# Bed_Temp_Controller.net
KiCad netlist of a schematic drawn in EAGLE
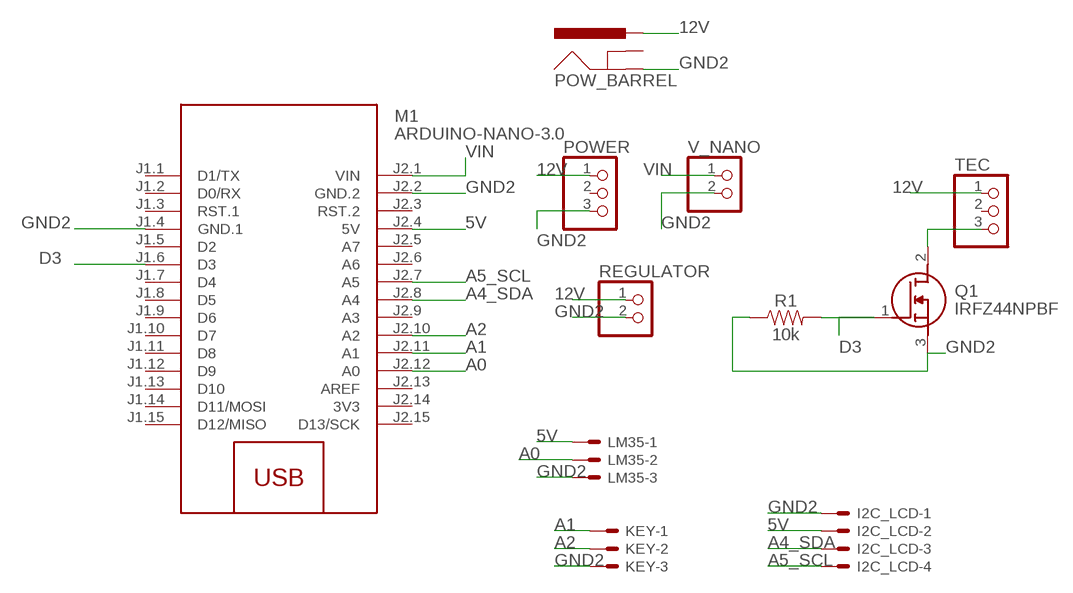
[diagram p0: schematic, sheet 1]

(export (version "E")
  (design (tool "Eeschema 10.0.6"))
  (components
    (comp (ref "I2C_LCD")
      (value "JST-XH-04-PIN-ROUND-PAD")
      (footprint "eagle-import:JST-XH-04-PACKAGE-ROUND-PAD")
      (libsource (lib "eagle-import") (part "JST-XH-04-PIN-ROUND-PAD"))
    )
    (comp (ref "KEY")
      (value "JST-XH-03-PIN-ROUND-PAD")
      (footprint "eagle-import:JST-XH-03-PACKAGE-ROUND-PAD")
      (libsource (lib "eagle-import") (part "JST-XH-03-PIN-ROUND-PAD"))
    )
    (comp (ref "LM35")
      (value "JST-XH-03-PIN-ROUND-PAD")
      (footprint "eagle-import:JST-XH-03-PACKAGE-ROUND-PAD")
      (libsource (lib "eagle-import") (part "JST-XH-03-PIN-ROUND-PAD"))
    )
    (comp (ref "M1")
      (value "ARDUINO-NANO-3.0")
      (footprint "eagle-import:ARDUINO-NANO-3.0")
      (libsource (lib "eagle-import") (part "ARDUINO-NANO-3.0"))
    )
    (comp (ref "POWER")
      (value "PINHD-1X3")
      (footprint "eagle-import:1X03")
      (libsource (lib "eagle-import") (part "PINHD-1X3"))
    )
    (comp (ref "POW_BARREL")
      (value "POWER_JACKPTH_BREAD")
      (footprint "eagle-import:POWER_JACK_PTH_BREAD")
      (libsource (lib "eagle-import") (part "POWER_JACKPTH_BREAD"))
    )
    (comp (ref "Q1")
      (value "IRFZ44NPBF")
      (footprint "eagle-import:TO254P483X1016X1994-3P")
      (libsource (lib "eagle-import") (part "IRFZ44NPBF"))
    )
    (comp (ref "R1")
      (value "10k")
      (footprint "eagle-import:AXIAL-0.3")
      (libsource (lib "eagle-import") (part "1KOHM-HORIZ-1/4W-1%"))
    )
    (comp (ref "REGULATOR")
      (value "PINHD-1X2")
      (footprint "eagle-import:1X02")
      (libsource (lib "eagle-import") (part "PINHD-1X2"))
    )
    (comp (ref "TEC")
      (value "PINHD-1X3")
      (footprint "eagle-import:1X03")
      (libsource (lib "eagle-import") (part "PINHD-1X3"))
    )
    (comp (ref "V_NANO")
      (value "PINHD-1X2")
      (footprint "eagle-import:1X02")
      (libsource (lib "eagle-import") (part "PINHD-1X2"))
    )
  )
  (nets
    (net (code "1") (name "3V3") (class "Default")
      (node (ref "M1") (pin "J2.14") (pinfunction "3V3_J2.14") (pintype "power_in"))
    )
    (net (code "2") (name "5V") (class "Default")
      (node (ref "I2C_LCD") (pin "2") (pinfunction "S_2") (pintype "passive"))
      (node (ref "LM35") (pin "1") (pinfunction "S_1") (pintype "passive"))
      (node (ref "M1") (pin "J2.4") (pinfunction "5V_J2.4") (pintype "power_in"))
    )
    (net (code "3") (name "12V") (class "Default")
      (node (ref "POWER") (pin "1") (pinfunction "1_1") (pintype "passive"))
      (node (ref "POW_BARREL") (pin "PWR") (pinfunction "PWR_PWR") (pintype "bidirectional"))
      (node (ref "REGULATOR") (pin "1") (pinfunction "1_1") (pintype "passive"))
      (node (ref "TEC") (pin "1") (pinfunction "1_1") (pintype "passive"))
    )
    (net (code "4") (name "A0") (class "Default")
      (node (ref "LM35") (pin "2") (pinfunction "S_2") (pintype "passive"))
      (node (ref "M1") (pin "J2.12") (pinfunction "A0_J2.12") (pintype "bidirectional"))
    )
    (net (code "5") (name "A1") (class "Default")
      (node (ref "KEY") (pin "1") (pinfunction "S_1") (pintype "passive"))
      (node (ref "M1") (pin "J2.11") (pinfunction "A1_J2.11") (pintype "bidirectional"))
    )
    (net (code "6") (name "A2") (class "Default")
      (node (ref "KEY") (pin "2") (pinfunction "S_2") (pintype "passive"))
      (node (ref "M1") (pin "J2.10") (pinfunction "A2_J2.10") (pintype "bidirectional"))
    )
    (net (code "7") (name "A4_SDA") (class "Default")
      (node (ref "I2C_LCD") (pin "3") (pinfunction "S_3") (pintype "passive"))
      (node (ref "M1") (pin "J2.8") (pinfunction "A4_J2.8") (pintype "bidirectional"))
    )
    (net (code "8") (name "A5_SCL") (class "Default")
      (node (ref "I2C_LCD") (pin "4") (pinfunction "S_4") (pintype "passive"))
      (node (ref "M1") (pin "J2.7") (pinfunction "A5_J2.7") (pintype "bidirectional"))
    )
    (net (code "9") (name "D3") (class "Default")
      (node (ref "M1") (pin "J1.6") (pinfunction "D3_J1.6") (pintype "bidirectional"))
      (node (ref "Q1") (pin "1") (pinfunction "G_1") (pintype "bidirectional"))
      (node (ref "R1") (pin "P$2") (pinfunction "2_P$2") (pintype "passive"))
    )
    (net (code "10") (name "GND2") (class "Default")
      (node (ref "I2C_LCD") (pin "1") (pinfunction "S_1") (pintype "passive"))
      (node (ref "KEY") (pin "3") (pinfunction "S_3") (pintype "passive"))
      (node (ref "LM35") (pin "3") (pinfunction "S_3") (pintype "passive"))
      (node (ref "M1") (pin "J1.4") (pinfunction "GND.1_J1.4") (pintype "power_in"))
      (node (ref "M1") (pin "J2.2") (pinfunction "GND.2_J2.2") (pintype "power_in"))
      (node (ref "POWER") (pin "3") (pinfunction "3_3") (pintype "passive"))
      (node (ref "POW_BARREL") (pin "GND") (pinfunction "GND_GND") (pintype "bidirectional"))
      (node (ref "Q1") (pin "3") (pinfunction "S_3") (pintype "bidirectional"))
      (node (ref "R1") (pin "P$1") (pinfunction "1_P$1") (pintype "passive"))
      (node (ref "REGULATOR") (pin "2") (pinfunction "2_2") (pintype "passive"))
      (node (ref "V_NANO") (pin "2") (pinfunction "2_2") (pintype "passive"))
    )
    (net (code "11") (name "Net-(Q1-D)") (class "Default")
      (node (ref "Q1") (pin "2") (pinfunction "D_2") (pintype "bidirectional"))
      (node (ref "TEC") (pin "3") (pinfunction "3_3") (pintype "passive"))
    )
    (net (code "12") (name "VIN") (class "Default")
      (node (ref "M1") (pin "J2.1") (pinfunction "VIN_J2.1") (pintype "power_in"))
      (node (ref "V_NANO") (pin "1") (pinfunction "1_1") (pintype "passive"))
    )
    (net (code "13") (name "unconnected-(M1-A3-PadJ2.9)") (class "Default")
      (node (ref "M1") (pin "J2.9") (pinfunction "A3_J2.9") (pintype "bidirectional"))
    )
    (net (code "14") (name "unconnected-(M1-A6-PadJ2.6)") (class "Default")
      (node (ref "M1") (pin "J2.6") (pinfunction "A6_J2.6") (pintype "bidirectional"))
    )
    (net (code "15") (name "unconnected-(M1-A7-PadJ2.5)") (class "Default")
      (node (ref "M1") (pin "J2.5") (pinfunction "A7_J2.5") (pintype "bidirectional"))
    )
    (net (code "16") (name "unconnected-(M1-AREF-PadJ2.13)") (class "Default")
      (node (ref "M1") (pin "J2.13") (pinfunction "AREF_J2.13") (pintype "bidirectional"))
    )
    (net (code "17") (name "unconnected-(M1-D0{slash}RX-PadJ1.2)") (class "Default")
      (node (ref "M1") (pin "J1.2") (pinfunction "D0/RX_J1.2") (pintype "bidirectional"))
    )
    (net (code "18") (name "unconnected-(M1-D1{slash}TX-PadJ1.1)") (class "Default")
      (node (ref "M1") (pin "J1.1") (pinfunction "D1/TX_J1.1") (pintype "bidirectional"))
    )
    (net (code "19") (name "unconnected-(M1-D2-PadJ1.5)") (class "Default")
      (node (ref "M1") (pin "J1.5") (pinfunction "D2_J1.5") (pintype "bidirectional"))
    )
    (net (code "20") (name "unconnected-(M1-D4-PadJ1.7)") (class "Default")
      (node (ref "M1") (pin "J1.7") (pinfunction "D4_J1.7") (pintype "bidirectional"))
    )
    (net (code "21") (name "unconnected-(M1-D5-PadJ1.8)") (class "Default")
      (node (ref "M1") (pin "J1.8") (pinfunction "D5_J1.8") (pintype "bidirectional"))
    )
    (net (code "22") (name "unconnected-(M1-D6-PadJ1.9)") (class "Default")
      (node (ref "M1") (pin "J1.9") (pinfunction "D6_J1.9") (pintype "bidirectional"))
    )
    (net (code "23") (name "unconnected-(M1-D7-PadJ1.10)") (class "Default")
      (node (ref "M1") (pin "J1.10") (pinfunction "D7_J1.10") (pintype "bidirectional"))
    )
    (net (code "24") (name "unconnected-(M1-D8-PadJ1.11)") (class "Default")
      (node (ref "M1") (pin "J1.11") (pinfunction "D8_J1.11") (pintype "bidirectional"))
    )
    (net (code "25") (name "unconnected-(M1-D9-PadJ1.12)") (class "Default")
      (node (ref "M1") (pin "J1.12") (pinfunction "D9_J1.12") (pintype "bidirectional"))
    )
    (net (code "26") (name "unconnected-(M1-D10-PadJ1.13)") (class "Default")
      (node (ref "M1") (pin "J1.13") (pinfunction "D10_J1.13") (pintype "bidirectional"))
    )
    (net (code "27") (name "unconnected-(M1-D11{slash}MOSI-PadJ1.14)") (class "Default")
      (node (ref "M1") (pin "J1.14") (pinfunction "D11/MOSI_J1.14") (pintype "bidirectional"))
    )
    (net (code "28") (name "unconnected-(M1-D12{slash}MISO-PadJ1.15)") (class "Default")
      (node (ref "M1") (pin "J1.15") (pinfunction "D12/MISO_J1.15") (pintype "bidirectional"))
    )
    (net (code "29") (name "unconnected-(M1-D13{slash}SCK-PadJ2.15)") (class "Default")
      (node (ref "M1") (pin "J2.15") (pinfunction "D13/SCK_J2.15") (pintype "bidirectional"))
    )
    (net (code "30") (name "unconnected-(M1-RST.1-PadJ1.3)") (class "Default")
      (node (ref "M1") (pin "J1.3") (pinfunction "RST.1_J1.3") (pintype "bidirectional"))
    )
    (net (code "31") (name "unconnected-(M1-RST.2-PadJ2.3)") (class "Default")
      (node (ref "M1") (pin "J2.3") (pinfunction "RST.2_J2.3") (pintype "bidirectional"))
    )
    (net (code "32") (name "unconnected-(POWER-Pad2)") (class "Default")
      (node (ref "POWER") (pin "2") (pinfunction "2_2") (pintype "passive"))
    )
    (net (code "33") (name "unconnected-(POW_BARREL-PadGNDBREAK)") (class "Default")
      (node (ref "POW_BARREL") (pin "GNDBREAK") (pinfunction "GNDBREAK_GNDBREAK") (pintype "bidirectional"))
    )
    (net (code "34") (name "unconnected-(TEC-Pad2)") (class "Default")
      (node (ref "TEC") (pin "2") (pinfunction "2_2") (pintype "passive"))
    )
  )
)
